# Pi_Header.net
KiCad netlist of a schematic drawn in EAGLE
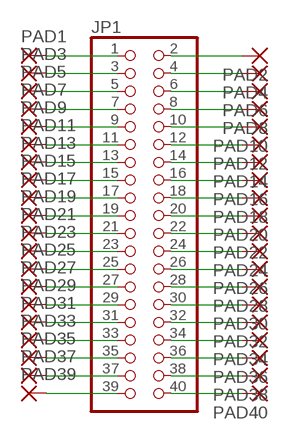
[diagram p0: schematic, sheet 1]

(export (version "E")
  (design (tool "Eeschema 10.0.6"))
  (components
    (comp (ref "JP1")
      (value "PINHD-2X20-BIG")
      (footprint "eagle-import:2X20-BIG")
      (libsource (lib "eagle-import") (part "PINHD-2X20-BIG"))
    )
    (comp (ref "PAD1")
      (value "1,6/0,8")
      (footprint "eagle-import:1,6_0,8")
      (libsource (lib "eagle-import") (part "1,6/0,8"))
    )
    (comp (ref "PAD2")
      (value "1,6/0,8")
      (footprint "eagle-import:1,6_0,8")
      (libsource (lib "eagle-import") (part "1,6/0,8"))
    )
    (comp (ref "PAD3")
      (value "1,6/0,8")
      (footprint "eagle-import:1,6_0,8")
      (libsource (lib "eagle-import") (part "1,6/0,8"))
    )
    (comp (ref "PAD4")
      (value "1,6/0,8")
      (footprint "eagle-import:1,6_0,8")
      (libsource (lib "eagle-import") (part "1,6/0,8"))
    )
    (comp (ref "PAD5")
      (value "1,6/0,8")
      (footprint "eagle-import:1,6_0,8")
      (libsource (lib "eagle-import") (part "1,6/0,8"))
    )
    (comp (ref "PAD6")
      (value "1,6/0,8")
      (footprint "eagle-import:1,6_0,8")
      (libsource (lib "eagle-import") (part "1,6/0,8"))
    )
    (comp (ref "PAD7")
      (value "1,6/0,8")
      (footprint "eagle-import:1,6_0,8")
      (libsource (lib "eagle-import") (part "1,6/0,8"))
    )
    (comp (ref "PAD8")
      (value "1,6/0,8")
      (footprint "eagle-import:1,6_0,8")
      (libsource (lib "eagle-import") (part "1,6/0,8"))
    )
    (comp (ref "PAD9")
      (value "1,6/0,8")
      (footprint "eagle-import:1,6_0,8")
      (libsource (lib "eagle-import") (part "1,6/0,8"))
    )
    (comp (ref "PAD10")
      (value "1,6/0,8")
      (footprint "eagle-import:1,6_0,8")
      (libsource (lib "eagle-import") (part "1,6/0,8"))
    )
    (comp (ref "PAD11")
      (value "1,6/0,8")
      (footprint "eagle-import:1,6_0,8")
      (libsource (lib "eagle-import") (part "1,6/0,8"))
    )
    (comp (ref "PAD12")
      (value "1,6/0,8")
      (footprint "eagle-import:1,6_0,8")
      (libsource (lib "eagle-import") (part "1,6/0,8"))
    )
    (comp (ref "PAD13")
      (value "1,6/0,8")
      (footprint "eagle-import:1,6_0,8")
      (libsource (lib "eagle-import") (part "1,6/0,8"))
    )
    (comp (ref "PAD14")
      (value "1,6/0,8")
      (footprint "eagle-import:1,6_0,8")
      (libsource (lib "eagle-import") (part "1,6/0,8"))
    )
    (comp (ref "PAD15")
      (value "1,6/0,8")
      (footprint "eagle-import:1,6_0,8")
      (libsource (lib "eagle-import") (part "1,6/0,8"))
    )
    (comp (ref "PAD16")
      (value "1,6/0,8")
      (footprint "eagle-import:1,6_0,8")
      (libsource (lib "eagle-import") (part "1,6/0,8"))
    )
    (comp (ref "PAD17")
      (value "1,6/0,8")
      (footprint "eagle-import:1,6_0,8")
      (libsource (lib "eagle-import") (part "1,6/0,8"))
    )
    (comp (ref "PAD18")
      (value "1,6/0,8")
      (footprint "eagle-import:1,6_0,8")
      (libsource (lib "eagle-import") (part "1,6/0,8"))
    )
    (comp (ref "PAD19")
      (value "1,6/0,8")
      (footprint "eagle-import:1,6_0,8")
      (libsource (lib "eagle-import") (part "1,6/0,8"))
    )
    (comp (ref "PAD20")
      (value "1,6/0,8")
      (footprint "eagle-import:1,6_0,8")
      (libsource (lib "eagle-import") (part "1,6/0,8"))
    )
    (comp (ref "PAD21")
      (value "1,6/0,8")
      (footprint "eagle-import:1,6_0,8")
      (libsource (lib "eagle-import") (part "1,6/0,8"))
    )
    (comp (ref "PAD22")
      (value "1,6/0,8")
      (footprint "eagle-import:1,6_0,8")
      (libsource (lib "eagle-import") (part "1,6/0,8"))
    )
    (comp (ref "PAD23")
      (value "1,6/0,8")
      (footprint "eagle-import:1,6_0,8")
      (libsource (lib "eagle-import") (part "1,6/0,8"))
    )
    (comp (ref "PAD24")
      (value "1,6/0,8")
      (footprint "eagle-import:1,6_0,8")
      (libsource (lib "eagle-import") (part "1,6/0,8"))
    )
    (comp (ref "PAD25")
      (value "1,6/0,8")
      (footprint "eagle-import:1,6_0,8")
      (libsource (lib "eagle-import") (part "1,6/0,8"))
    )
    (comp (ref "PAD26")
      (value "1,6/0,8")
      (footprint "eagle-import:1,6_0,8")
      (libsource (lib "eagle-import") (part "1,6/0,8"))
    )
    (comp (ref "PAD27")
      (value "1,6/0,8")
      (footprint "eagle-import:1,6_0,8")
      (libsource (lib "eagle-import") (part "1,6/0,8"))
    )
    (comp (ref "PAD28")
      (value "1,6/0,8")
      (footprint "eagle-import:1,6_0,8")
      (libsource (lib "eagle-import") (part "1,6/0,8"))
    )
    (comp (ref "PAD29")
      (value "1,6/0,8")
      (footprint "eagle-import:1,6_0,8")
      (libsource (lib "eagle-import") (part "1,6/0,8"))
    )
    (comp (ref "PAD30")
      (value "1,6/0,8")
      (footprint "eagle-import:1,6_0,8")
      (libsource (lib "eagle-import") (part "1,6/0,8"))
    )
    (comp (ref "PAD31")
      (value "1,6/0,8")
      (footprint "eagle-import:1,6_0,8")
      (libsource (lib "eagle-import") (part "1,6/0,8"))
    )
    (comp (ref "PAD32")
      (value "1,6/0,8")
      (footprint "eagle-import:1,6_0,8")
      (libsource (lib "eagle-import") (part "1,6/0,8"))
    )
    (comp (ref "PAD33")
      (value "1,6/0,8")
      (footprint "eagle-import:1,6_0,8")
      (libsource (lib "eagle-import") (part "1,6/0,8"))
    )
    (comp (ref "PAD34")
      (value "1,6/0,8")
      (footprint "eagle-import:1,6_0,8")
      (libsource (lib "eagle-import") (part "1,6/0,8"))
    )
    (comp (ref "PAD35")
      (value "1,6/0,8")
      (footprint "eagle-import:1,6_0,8")
      (libsource (lib "eagle-import") (part "1,6/0,8"))
    )
    (comp (ref "PAD36")
      (value "1,6/0,8")
      (footprint "eagle-import:1,6_0,8")
      (libsource (lib "eagle-import") (part "1,6/0,8"))
    )
    (comp (ref "PAD37")
      (value "1,6/0,8")
      (footprint "eagle-import:1,6_0,8")
      (libsource (lib "eagle-import") (part "1,6/0,8"))
    )
    (comp (ref "PAD38")
      (value "1,6/0,8")
      (footprint "eagle-import:1,6_0,8")
      (libsource (lib "eagle-import") (part "1,6/0,8"))
    )
    (comp (ref "PAD39")
      (value "1,6/0,8")
      (footprint "eagle-import:1,6_0,8")
      (libsource (lib "eagle-import") (part "1,6/0,8"))
    )
    (comp (ref "PAD40")
      (value "1,6/0,8")
      (footprint "eagle-import:1,6_0,8")
      (libsource (lib "eagle-import") (part "1,6/0,8"))
    )
  )
  (nets
    (net (code "1") (name "Net-(PAD1-P)") (class "Default")
      (node (ref "JP1") (pin "1") (pinfunction "1_1") (pintype "passive"))
      (node (ref "PAD1") (pin "1") (pinfunction "P_1") (pintype "passive"))
    )
    (net (code "2") (name "Net-(PAD2-P)") (class "Default")
      (node (ref "JP1") (pin "2") (pinfunction "2_2") (pintype "passive"))
      (node (ref "PAD2") (pin "1") (pinfunction "P_1") (pintype "passive"))
    )
    (net (code "3") (name "Net-(PAD3-P)") (class "Default")
      (node (ref "JP1") (pin "3") (pinfunction "3_3") (pintype "passive"))
      (node (ref "PAD3") (pin "1") (pinfunction "P_1") (pintype "passive"))
    )
    (net (code "4") (name "Net-(PAD4-P)") (class "Default")
      (node (ref "JP1") (pin "4") (pinfunction "4_4") (pintype "passive"))
      (node (ref "PAD4") (pin "1") (pinfunction "P_1") (pintype "passive"))
    )
    (net (code "5") (name "Net-(PAD5-P)") (class "Default")
      (node (ref "JP1") (pin "5") (pinfunction "5_5") (pintype "passive"))
      (node (ref "PAD5") (pin "1") (pinfunction "P_1") (pintype "passive"))
    )
    (net (code "6") (name "Net-(PAD6-P)") (class "Default")
      (node (ref "JP1") (pin "6") (pinfunction "6_6") (pintype "passive"))
      (node (ref "PAD6") (pin "1") (pinfunction "P_1") (pintype "passive"))
    )
    (net (code "7") (name "Net-(PAD7-P)") (class "Default")
      (node (ref "JP1") (pin "7") (pinfunction "7_7") (pintype "passive"))
      (node (ref "PAD7") (pin "1") (pinfunction "P_1") (pintype "passive"))
    )
    (net (code "8") (name "Net-(PAD8-P)") (class "Default")
      (node (ref "JP1") (pin "8") (pinfunction "8_8") (pintype "passive"))
      (node (ref "PAD8") (pin "1") (pinfunction "P_1") (pintype "passive"))
    )
    (net (code "9") (name "Net-(PAD9-P)") (class "Default")
      (node (ref "JP1") (pin "9") (pinfunction "9_9") (pintype "passive"))
      (node (ref "PAD9") (pin "1") (pinfunction "P_1") (pintype "passive"))
    )
    (net (code "10") (name "Net-(PAD10-P)") (class "Default")
      (node (ref "JP1") (pin "10") (pinfunction "10_10") (pintype "passive"))
      (node (ref "PAD10") (pin "1") (pinfunction "P_1") (pintype "passive"))
    )
    (net (code "11") (name "Net-(PAD11-P)") (class "Default")
      (node (ref "JP1") (pin "11") (pinfunction "11_11") (pintype "passive"))
      (node (ref "PAD11") (pin "1") (pinfunction "P_1") (pintype "passive"))
    )
    (net (code "12") (name "Net-(PAD12-P)") (class "Default")
      (node (ref "JP1") (pin "12") (pinfunction "12_12") (pintype "passive"))
      (node (ref "PAD12") (pin "1") (pinfunction "P_1") (pintype "passive"))
    )
    (net (code "13") (name "Net-(PAD13-P)") (class "Default")
      (node (ref "JP1") (pin "13") (pinfunction "13_13") (pintype "passive"))
      (node (ref "PAD13") (pin "1") (pinfunction "P_1") (pintype "passive"))
    )
    (net (code "14") (name "Net-(PAD14-P)") (class "Default")
      (node (ref "JP1") (pin "14") (pinfunction "14_14") (pintype "passive"))
      (node (ref "PAD14") (pin "1") (pinfunction "P_1") (pintype "passive"))
    )
    (net (code "15") (name "Net-(PAD15-P)") (class "Default")
      (node (ref "JP1") (pin "15") (pinfunction "15_15") (pintype "passive"))
      (node (ref "PAD15") (pin "1") (pinfunction "P_1") (pintype "passive"))
    )
    (net (code "16") (name "Net-(PAD16-P)") (class "Default")
      (node (ref "JP1") (pin "16") (pinfunction "16_16") (pintype "passive"))
      (node (ref "PAD16") (pin "1") (pinfunction "P_1") (pintype "passive"))
    )
    (net (code "17") (name "Net-(PAD17-P)") (class "Default")
      (node (ref "JP1") (pin "17") (pinfunction "17_17") (pintype "passive"))
      (node (ref "PAD17") (pin "1") (pinfunction "P_1") (pintype "passive"))
    )
    (net (code "18") (name "Net-(PAD18-P)") (class "Default")
      (node (ref "JP1") (pin "18") (pinfunction "18_18") (pintype "passive"))
      (node (ref "PAD18") (pin "1") (pinfunction "P_1") (pintype "passive"))
    )
    (net (code "19") (name "Net-(PAD19-P)") (class "Default")
      (node (ref "JP1") (pin "19") (pinfunction "19_19") (pintype "passive"))
      (node (ref "PAD19") (pin "1") (pinfunction "P_1") (pintype "passive"))
    )
    (net (code "20") (name "Net-(PAD20-P)") (class "Default")
      (node (ref "JP1") (pin "20") (pinfunction "20_20") (pintype "passive"))
      (node (ref "PAD20") (pin "1") (pinfunction "P_1") (pintype "passive"))
    )
    (net (code "21") (name "Net-(PAD21-P)") (class "Default")
      (node (ref "JP1") (pin "21") (pinfunction "21_21") (pintype "passive"))
      (node (ref "PAD21") (pin "1") (pinfunction "P_1") (pintype "passive"))
    )
    (net (code "22") (name "Net-(PAD22-P)") (class "Default")
      (node (ref "JP1") (pin "22") (pinfunction "22_22") (pintype "passive"))
      (node (ref "PAD22") (pin "1") (pinfunction "P_1") (pintype "passive"))
    )
    (net (code "23") (name "Net-(PAD23-P)") (class "Default")
      (node (ref "JP1") (pin "23") (pinfunction "23_23") (pintype "passive"))
      (node (ref "PAD23") (pin "1") (pinfunction "P_1") (pintype "passive"))
    )
    (net (code "24") (name "Net-(PAD24-P)") (class "Default")
      (node (ref "JP1") (pin "24") (pinfunction "24_24") (pintype "passive"))
      (node (ref "PAD24") (pin "1") (pinfunction "P_1") (pintype "passive"))
    )
    (net (code "25") (name "Net-(PAD25-P)") (class "Default")
      (node (ref "JP1") (pin "25") (pinfunction "25_25") (pintype "passive"))
      (node (ref "PAD25") (pin "1") (pinfunction "P_1") (pintype "passive"))
    )
    (net (code "26") (name "Net-(PAD26-P)") (class "Default")
      (node (ref "JP1") (pin "26") (pinfunction "26_26") (pintype "passive"))
      (node (ref "PAD26") (pin "1") (pinfunction "P_1") (pintype "passive"))
    )
    (net (code "27") (name "Net-(PAD27-P)") (class "Default")
      (node (ref "JP1") (pin "27") (pinfunction "27_27") (pintype "passive"))
      (node (ref "PAD27") (pin "1") (pinfunction "P_1") (pintype "passive"))
    )
    (net (code "28") (name "Net-(PAD28-P)") (class "Default")
      (node (ref "JP1") (pin "28") (pinfunction "28_28") (pintype "passive"))
      (node (ref "PAD28") (pin "1") (pinfunction "P_1") (pintype "passive"))
    )
    (net (code "29") (name "Net-(PAD29-P)") (class "Default")
      (node (ref "JP1") (pin "29") (pinfunction "29_29") (pintype "passive"))
      (node (ref "PAD29") (pin "1") (pinfunction "P_1") (pintype "passive"))
    )
    (net (code "30") (name "Net-(PAD30-P)") (class "Default")
      (node (ref "JP1") (pin "30") (pinfunction "30_30") (pintype "passive"))
      (node (ref "PAD30") (pin "1") (pinfunction "P_1") (pintype "passive"))
    )
    (net (code "31") (name "Net-(PAD31-P)") (class "Default")
      (node (ref "JP1") (pin "31") (pinfunction "31_31") (pintype "passive"))
      (node (ref "PAD31") (pin "1") (pinfunction "P_1") (pintype "passive"))
    )
    (net (code "32") (name "Net-(PAD32-P)") (class "Default")
      (node (ref "JP1") (pin "32") (pinfunction "32_32") (pintype "passive"))
      (node (ref "PAD32") (pin "1") (pinfunction "P_1") (pintype "passive"))
    )
    (net (code "33") (name "Net-(PAD33-P)") (class "Default")
      (node (ref "JP1") (pin "33") (pinfunction "33_33") (pintype "passive"))
      (node (ref "PAD33") (pin "1") (pinfunction "P_1") (pintype "passive"))
    )
    (net (code "34") (name "Net-(PAD34-P)") (class "Default")
      (node (ref "JP1") (pin "34") (pinfunction "34_34") (pintype "passive"))
      (node (ref "PAD34") (pin "1") (pinfunction "P_1") (pintype "passive"))
    )
    (net (code "35") (name "Net-(PAD35-P)") (class "Default")
      (node (ref "JP1") (pin "35") (pinfunction "35_35") (pintype "passive"))
      (node (ref "PAD35") (pin "1") (pinfunction "P_1") (pintype "passive"))
    )
    (net (code "36") (name "Net-(PAD36-P)") (class "Default")
      (node (ref "JP1") (pin "36") (pinfunction "36_36") (pintype "passive"))
      (node (ref "PAD36") (pin "1") (pinfunction "P_1") (pintype "passive"))
    )
    (net (code "37") (name "Net-(PAD37-P)") (class "Default")
      (node (ref "JP1") (pin "37") (pinfunction "37_37") (pintype "passive"))
      (node (ref "PAD37") (pin "1") (pinfunction "P_1") (pintype "passive"))
    )
    (net (code "38") (name "Net-(PAD38-P)") (class "Default")
      (node (ref "JP1") (pin "38") (pinfunction "38_38") (pintype "passive"))
      (node (ref "PAD38") (pin "1") (pinfunction "P_1") (pintype "passive"))
    )
    (net (code "39") (name "Net-(PAD39-P)") (class "Default")
      (node (ref "JP1") (pin "39") (pinfunction "39_39") (pintype "passive"))
      (node (ref "PAD39") (pin "1") (pinfunction "P_1") (pintype "passive"))
    )
    (net (code "40") (name "Net-(PAD40-P)") (class "Default")
      (node (ref "JP1") (pin "40") (pinfunction "40_40") (pintype "passive"))
      (node (ref "PAD40") (pin "1") (pinfunction "P_1") (pintype "passive"))
    )
  )
)
